# steve.net
KiCad netlist of a schematic drawn in EAGLE
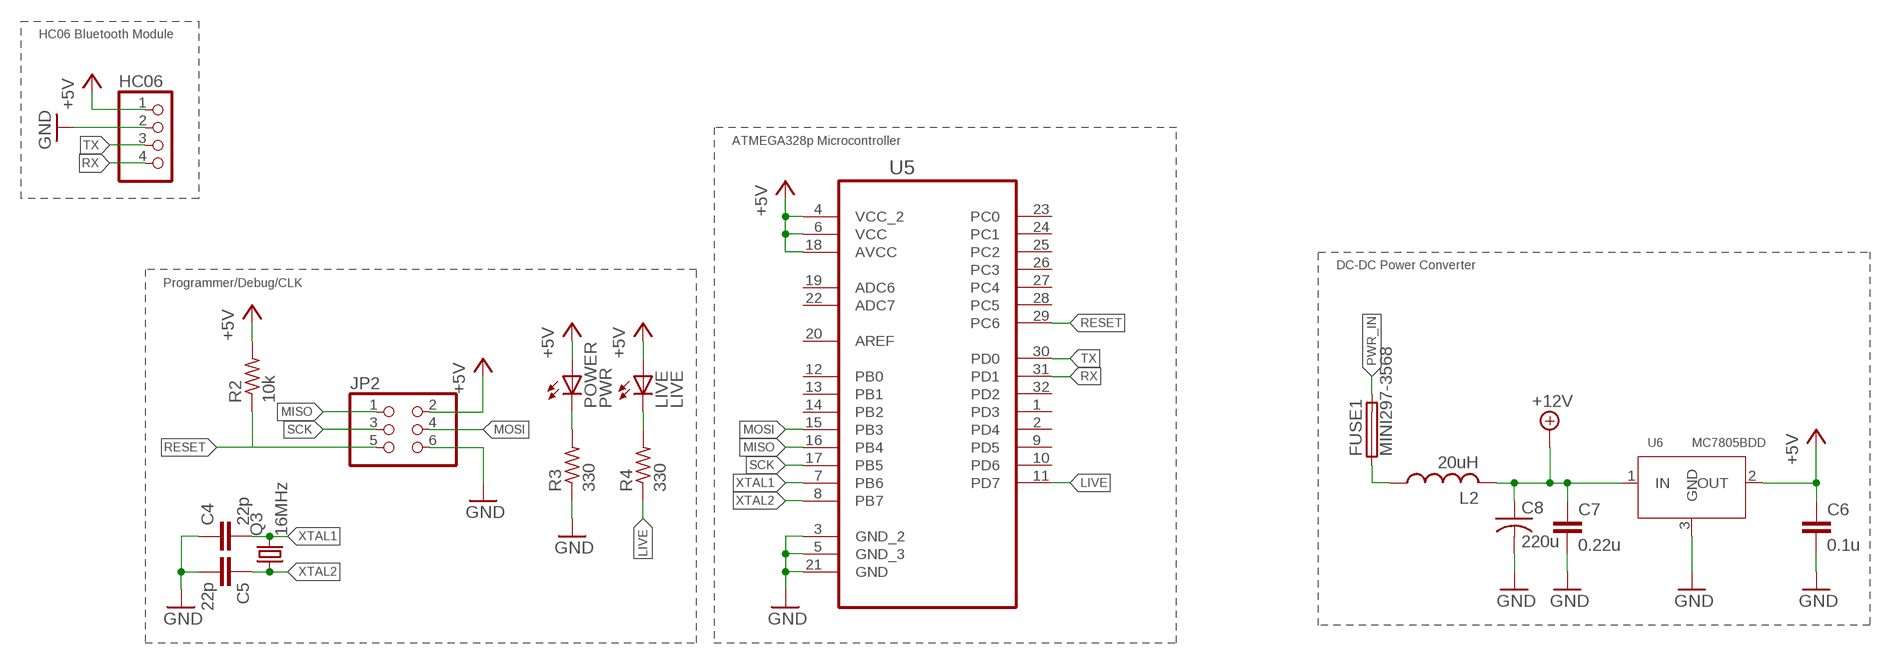
[diagram p0: schematic, sheet 1]

(export (version "E")
  (design (tool "Eeschema 10.0.6"))
  (components
    (comp (ref "C4")
      (value "22p")
      (footprint "eagle-import:C0805K")
      (libsource (lib "eagle-import") (part "resistor_C-EUC0805K"))
    )
    (comp (ref "C5")
      (value "22p")
      (footprint "eagle-import:C0805K")
      (libsource (lib "eagle-import") (part "resistor_C-EUC0805K"))
    )
    (comp (ref "C6")
      (value "0.1u")
      (footprint "eagle-import:C0805K")
      (libsource (lib "eagle-import") (part "C-EUC0805K"))
    )
    (comp (ref "C7")
      (value "0.22u")
      (footprint "eagle-import:C0805K")
      (libsource (lib "eagle-import") (part "C-EUC0805K"))
    )
    (comp (ref "C8")
      (value "220u")
      (footprint "eagle-import:C1206")
      (libsource (lib "eagle-import") (part "C1206"))
    )
    (comp (ref "FUSE1")
      (value "MINI297-3568")
      (footprint "eagle-import:3568")
      (libsource (lib "eagle-import") (part "MINI297-3568"))
    )
    (comp (ref "HC06")
      (value "PINHD-1X4")
      (footprint "eagle-import:1X04")
      (libsource (lib "eagle-import") (part "PINHD-1X4"))
    )
    (comp (ref "JP2")
      (value "PINHD-2X3")
      (footprint "eagle-import:2X03")
      (libsource (lib "eagle-import") (part "PINHD-2X3"))
    )
    (comp (ref "L2")
      (value "20uH")
      (footprint "eagle-import:MSS7348")
      (libsource (lib "eagle-import") (part "MSS7348"))
    )
    (comp (ref "LIVE")
      (value "LIVE")
      (footprint "eagle-import:SML0805")
      (libsource (lib "eagle-import") (part "LEDSML0805"))
    )
    (comp (ref "POWER")
      (value "PWR")
      (footprint "eagle-import:SML0805")
      (libsource (lib "eagle-import") (part "LEDSML0805"))
    )
    (comp (ref "Q3")
      (value "16MHz")
      (footprint "eagle-import:CTS406")
      (libsource (lib "eagle-import") (part "CRYSTALCTS406"))
    )
    (comp (ref "R2")
      (value "10k")
      (footprint "eagle-import:R0805")
      (libsource (lib "eagle-import") (part "R-US_R0805"))
    )
    (comp (ref "R3")
      (value "330")
      (footprint "eagle-import:R0805")
      (libsource (lib "eagle-import") (part "R-US_R0805"))
    )
    (comp (ref "R4")
      (value "330")
      (footprint "eagle-import:R0805")
      (libsource (lib "eagle-import") (part "R-US_R0805"))
    )
    (comp (ref "U5")
      (value "ATMEGA328P-AU")
      (footprint "eagle-import:QFP80P900X900X120-32N")
      (libsource (lib "eagle-import") (part "ATMEGA328P-AU"))
    )
    (comp (ref "U6")
      (value "MC7805BDD")
      (footprint "eagle-import:DPAK")
      (libsource (lib "eagle-import") (part "MC7805BDD"))
    )
  )
  (nets
    (net (code "1") (name "+5V") (class "Default")
      (node (ref "C6") (pin "1") (pinfunction "1_1") (pintype "passive"))
      (node (ref "HC06") (pin "1") (pinfunction "1_1") (pintype "passive"))
      (node (ref "JP2") (pin "2") (pinfunction "2_2") (pintype "passive"))
      (node (ref "LIVE") (pin "A") (pinfunction "A_A") (pintype "passive"))
      (node (ref "POWER") (pin "A") (pinfunction "A_A") (pintype "passive"))
      (node (ref "R2") (pin "2") (pinfunction "2_2") (pintype "passive"))
      (node (ref "U5") (pin "18") (pinfunction "AVCC_18") (pintype "power_in"))
      (node (ref "U5") (pin "4") (pinfunction "VCC_2_4") (pintype "power_in"))
      (node (ref "U5") (pin "6") (pinfunction "VCC_6") (pintype "power_in"))
      (node (ref "U6") (pin "2") (pinfunction "OUT_2") (pintype "bidirectional"))
    )
    (net (code "2") (name "+12V") (class "Default")
      (node (ref "C7") (pin "1") (pinfunction "1_1") (pintype "passive"))
      (node (ref "C8") (pin "1") (pinfunction "1_1") (pintype "passive"))
      (node (ref "L2") (pin "P$2") (pinfunction "2_P$2") (pintype "passive"))
      (node (ref "U6") (pin "1") (pinfunction "IN_1") (pintype "bidirectional"))
    )
    (net (code "3") (name "GND") (class "Default")
      (node (ref "C4") (pin "1") (pinfunction "1_1") (pintype "passive"))
      (node (ref "C5") (pin "2") (pinfunction "2_2") (pintype "passive"))
      (node (ref "C6") (pin "2") (pinfunction "2_2") (pintype "passive"))
      (node (ref "C7") (pin "2") (pinfunction "2_2") (pintype "passive"))
      (node (ref "C8") (pin "2") (pinfunction "2_2") (pintype "passive"))
      (node (ref "HC06") (pin "2") (pinfunction "2_2") (pintype "passive"))
      (node (ref "JP2") (pin "6") (pinfunction "6_6") (pintype "passive"))
      (node (ref "R3") (pin "1") (pinfunction "1_1") (pintype "passive"))
      (node (ref "U5") (pin "21") (pinfunction "GND_21") (pintype "passive"))
      (node (ref "U5") (pin "3") (pinfunction "GND_2_3") (pintype "passive"))
      (node (ref "U5") (pin "5") (pinfunction "GND_3_5") (pintype "passive"))
      (node (ref "U6") (pin "3") (pinfunction "GND_3") (pintype "bidirectional"))
    )
    (net (code "4") (name "LIVE") (class "Default")
      (node (ref "R4") (pin "1") (pinfunction "1_1") (pintype "passive"))
      (node (ref "U5") (pin "11") (pinfunction "PD7_11") (pintype "bidirectional"))
    )
    (net (code "5") (name "MISO") (class "Default")
      (node (ref "JP2") (pin "1") (pinfunction "1_1") (pintype "passive"))
      (node (ref "U5") (pin "16") (pinfunction "PB4_16") (pintype "bidirectional"))
    )
    (net (code "6") (name "MOSI") (class "Default")
      (node (ref "JP2") (pin "4") (pinfunction "4_4") (pintype "passive"))
      (node (ref "U5") (pin "15") (pinfunction "PB3_15") (pintype "bidirectional"))
    )
    (net (code "7") (name "Net-(LIVE-PadC)") (class "Default")
      (node (ref "LIVE") (pin "C") (pinfunction "C_C") (pintype "passive"))
      (node (ref "R4") (pin "2") (pinfunction "2_2") (pintype "passive"))
    )
    (net (code "8") (name "Net-(POWER-PadC)") (class "Default")
      (node (ref "POWER") (pin "C") (pinfunction "C_C") (pintype "passive"))
      (node (ref "R3") (pin "2") (pinfunction "2_2") (pintype "passive"))
    )
    (net (code "9") (name "PWR_IN") (class "Default")
      (node (ref "FUSE1") (pin "P$1") (pinfunction "1_P$1") (pintype "passive"))
      (node (ref "FUSE1") (pin "P$2") (pinfunction "2_P$2") (pintype "passive"))
      (node (ref "FUSE1") (pin "P$3") (pinfunction "2_P$3") (pintype "passive"))
      (node (ref "FUSE1") (pin "P$4") (pinfunction "1_P$4") (pintype "passive"))
      (node (ref "L2") (pin "P$1") (pinfunction "1_P$1") (pintype "passive"))
    )
    (net (code "10") (name "RESET") (class "Default")
      (node (ref "JP2") (pin "5") (pinfunction "5_5") (pintype "passive"))
      (node (ref "R2") (pin "1") (pinfunction "1_1") (pintype "passive"))
      (node (ref "U5") (pin "29") (pinfunction "PC6_29") (pintype "bidirectional"))
    )
    (net (code "11") (name "RX") (class "Default")
      (node (ref "HC06") (pin "4") (pinfunction "4_4") (pintype "passive"))
      (node (ref "U5") (pin "31") (pinfunction "PD1_31") (pintype "bidirectional"))
    )
    (net (code "12") (name "SCK") (class "Default")
      (node (ref "JP2") (pin "3") (pinfunction "3_3") (pintype "passive"))
      (node (ref "U5") (pin "17") (pinfunction "PB5_17") (pintype "bidirectional"))
    )
    (net (code "13") (name "TX") (class "Default")
      (node (ref "HC06") (pin "3") (pinfunction "3_3") (pintype "passive"))
      (node (ref "U5") (pin "30") (pinfunction "PD0_30") (pintype "bidirectional"))
    )
    (net (code "14") (name "XTAL1") (class "Default")
      (node (ref "C4") (pin "2") (pinfunction "2_2") (pintype "passive"))
      (node (ref "Q3") (pin "3") (pinfunction "2_3") (pintype "passive"))
      (node (ref "U5") (pin "7") (pinfunction "PB6_7") (pintype "bidirectional"))
    )
    (net (code "15") (name "XTAL2") (class "Default")
      (node (ref "C5") (pin "1") (pinfunction "1_1") (pintype "passive"))
      (node (ref "Q3") (pin "1") (pinfunction "1_1") (pintype "passive"))
      (node (ref "U5") (pin "8") (pinfunction "PB7_8") (pintype "bidirectional"))
    )
    (net (code "16") (name "unconnected-(U5-ADC6-Pad19)") (class "Default")
      (node (ref "U5") (pin "19") (pinfunction "ADC6_19") (pintype "input"))
    )
    (net (code "17") (name "unconnected-(U5-ADC7-Pad22)") (class "Default")
      (node (ref "U5") (pin "22") (pinfunction "ADC7_22") (pintype "input"))
    )
    (net (code "18") (name "unconnected-(U5-AREF-Pad20)") (class "Default")
      (node (ref "U5") (pin "20") (pinfunction "AREF_20") (pintype "input"))
    )
    (net (code "19") (name "unconnected-(U5-PB0-Pad12)") (class "Default")
      (node (ref "U5") (pin "12") (pinfunction "PB0_12") (pintype "bidirectional"))
    )
    (net (code "20") (name "unconnected-(U5-PB1-Pad13)") (class "Default")
      (node (ref "U5") (pin "13") (pinfunction "PB1_13") (pintype "bidirectional"))
    )
    (net (code "21") (name "unconnected-(U5-PB2-Pad14)") (class "Default")
      (node (ref "U5") (pin "14") (pinfunction "PB2_14") (pintype "bidirectional"))
    )
    (net (code "22") (name "unconnected-(U5-PC0-Pad23)") (class "Default")
      (node (ref "U5") (pin "23") (pinfunction "PC0_23") (pintype "bidirectional"))
    )
    (net (code "23") (name "unconnected-(U5-PC1-Pad24)") (class "Default")
      (node (ref "U5") (pin "24") (pinfunction "PC1_24") (pintype "bidirectional"))
    )
    (net (code "24") (name "unconnected-(U5-PC2-Pad25)") (class "Default")
      (node (ref "U5") (pin "25") (pinfunction "PC2_25") (pintype "bidirectional"))
    )
    (net (code "25") (name "unconnected-(U5-PC3-Pad26)") (class "Default")
      (node (ref "U5") (pin "26") (pinfunction "PC3_26") (pintype "bidirectional"))
    )
    (net (code "26") (name "unconnected-(U5-PC4-Pad27)") (class "Default")
      (node (ref "U5") (pin "27") (pinfunction "PC4_27") (pintype "bidirectional"))
    )
    (net (code "27") (name "unconnected-(U5-PC5-Pad28)") (class "Default")
      (node (ref "U5") (pin "28") (pinfunction "PC5_28") (pintype "bidirectional"))
    )
    (net (code "28") (name "unconnected-(U5-PD2-Pad32)") (class "Default")
      (node (ref "U5") (pin "32") (pinfunction "PD2_32") (pintype "bidirectional"))
    )
    (net (code "29") (name "unconnected-(U5-PD3-Pad1)") (class "Default")
      (node (ref "U5") (pin "1") (pinfunction "PD3_1") (pintype "bidirectional"))
    )
    (net (code "30") (name "unconnected-(U5-PD4-Pad2)") (class "Default")
      (node (ref "U5") (pin "2") (pinfunction "PD4_2") (pintype "bidirectional"))
    )
    (net (code "31") (name "unconnected-(U5-PD5-Pad9)") (class "Default")
      (node (ref "U5") (pin "9") (pinfunction "PD5_9") (pintype "bidirectional"))
    )
    (net (code "32") (name "unconnected-(U5-PD6-Pad10)") (class "Default")
      (node (ref "U5") (pin "10") (pinfunction "PD6_10") (pintype "bidirectional"))
    )
  )
)
